# OutputConnectors.net
KiCad netlist of a schematic drawn in Altium Designer
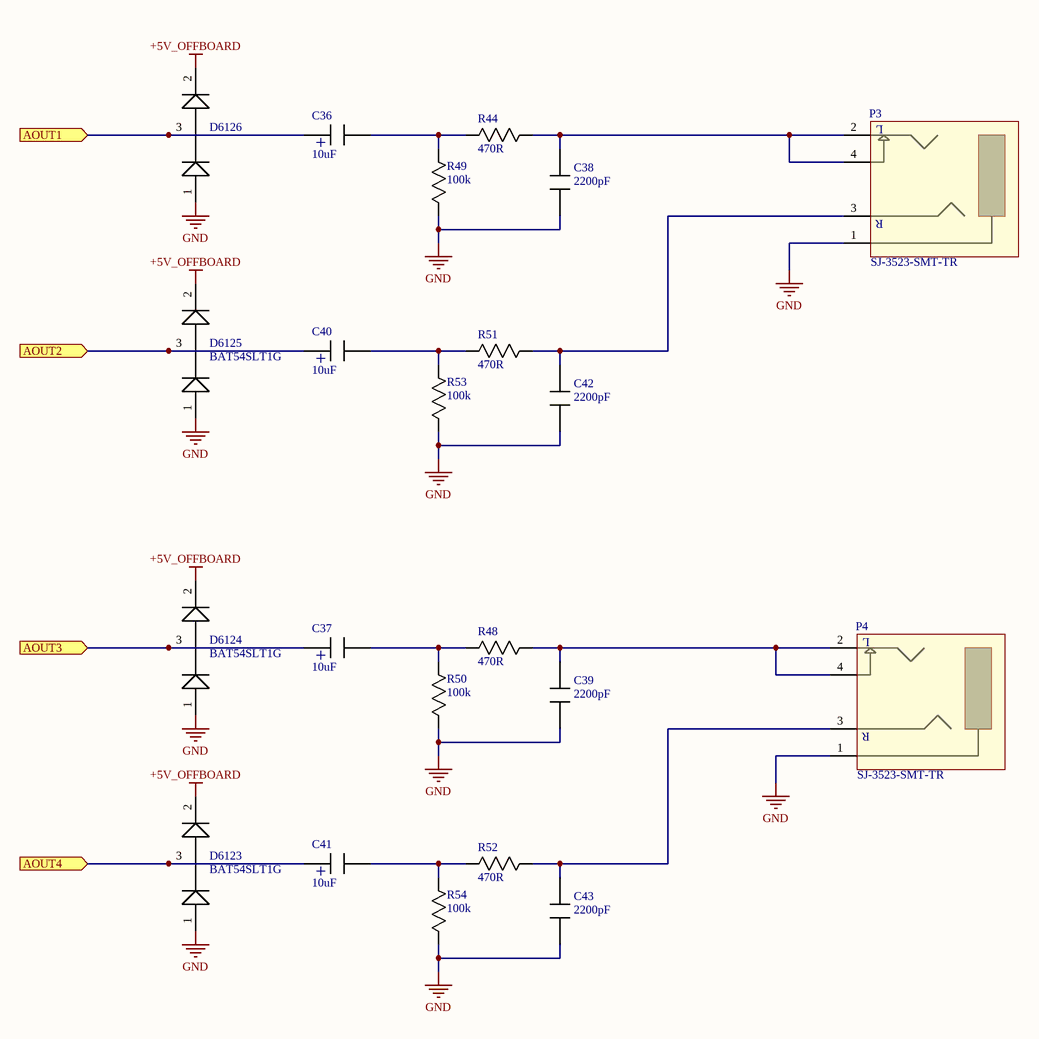
[diagram p0: OutputConnectors.SchDoc]

(export (version "E")
  (design (tool "Eeschema 10.0.6"))
  (components
    (comp (ref "C36")
      (value "10uF")
      (footprint "CAP_RAD_SMD_DIA157")
      (description "Capacitor")
      (fields (field (name "Comment") "Capacitor_Polarized"))
      (libsource (lib "INTER_2014") (part "Capacitor_Polarized"))
    )
    (comp (ref "C37")
      (value "10uF")
      (footprint "CAP_RAD_SMD_DIA157")
      (description "Capacitor")
      (fields (field (name "Comment") "Capacitor_Polarized"))
      (libsource (lib "INTER_2014") (part "Capacitor_Polarized"))
    )
    (comp (ref "C38")
      (value "2200pF")
      (footprint "0603")
      (description "Capacitor")
      (libsource (lib "INTER_2014") (part "Capacitor"))
    )
    (comp (ref "C39")
      (value "2200pF")
      (footprint "0603")
      (description "Capacitor")
      (libsource (lib "INTER_2014") (part "Capacitor"))
    )
    (comp (ref "C40")
      (value "10uF")
      (footprint "CAP_RAD_SMD_DIA157")
      (description "Capacitor")
      (fields (field (name "Comment") "Capacitor_Polarized"))
      (libsource (lib "INTER_2014") (part "Capacitor_Polarized"))
    )
    (comp (ref "C41")
      (value "10uF")
      (footprint "CAP_RAD_SMD_DIA157")
      (description "Capacitor")
      (fields (field (name "Comment") "Capacitor_Polarized"))
      (libsource (lib "INTER_2014") (part "Capacitor_Polarized"))
    )
    (comp (ref "C42")
      (value "2200pF")
      (footprint "0603")
      (description "Capacitor")
      (libsource (lib "INTER_2014") (part "Capacitor"))
    )
    (comp (ref "C43")
      (value "2200pF")
      (footprint "0603")
      (description "Capacitor")
      (libsource (lib "INTER_2014") (part "Capacitor"))
    )
    (comp (ref "D6123")
      (value "Diode_dual")
      (footprint "SOT23_132")
      (description "Diode")
      (fields (field (name "MFG") "Onsemi") (field (name "MFG_PN") "BAT54SLT1G"))
      (libsource (lib "INTER_2014") (part "Diode_dual"))
    )
    (comp (ref "D6124")
      (value "Diode_dual")
      (footprint "SOT23_132")
      (description "Diode")
      (fields (field (name "MFG") "Onsemi") (field (name "MFG_PN") "BAT54SLT1G"))
      (libsource (lib "INTER_2014") (part "Diode_dual"))
    )
    (comp (ref "D6125")
      (value "Diode_dual")
      (footprint "SOT23_132")
      (description "Diode")
      (fields (field (name "MFG") "Onsemi") (field (name "MFG_PN") "BAT54SLT1G"))
      (libsource (lib "INTER_2014") (part "Diode_dual"))
    )
    (comp (ref "D6126")
      (value "Diode_dual")
      (footprint "SOT23_132")
      (description "Diode")
      (fields (field (name "MFG") "Onsemi"))
      (libsource (lib "INTER_2014") (part "Diode_dual"))
    )
    (comp (ref "P3")
      (value "CON_AUDIO_3.5mm_TRS_ALT1")
      (footprint "CONN_3.5mm_CUI 3523-SMT")
      (description "Audio 3.5mm CUI SJ-3523-SMT-TR")
      (fields (field (name "MFG") "CUI") (field (name "MFG_PN") "SJ-3523-SMT-TR"))
      (libsource (lib "INTER_2014") (part "CON_AUDIO_3.5mm_TRS_ALT1"))
    )
    (comp (ref "P4")
      (value "CON_AUDIO_3.5mm_TRS_ALT1")
      (footprint "CONN_3.5mm_CUI 3523-SMT")
      (description "Audio 3.5mm CUI SJ-3523-SMT-TR")
      (fields (field (name "MFG") "CUI") (field (name "MFG_PN") "SJ-3523-SMT-TR"))
      (libsource (lib "INTER_2014") (part "CON_AUDIO_3.5mm_TRS_ALT1"))
    )
    (comp (ref "R44")
      (value "470R")
      (footprint "0603")
      (description "Resistor")
      (libsource (lib "INTER_2014") (part "Resistor"))
    )
    (comp (ref "R48")
      (value "470R")
      (footprint "0603")
      (description "Resistor")
      (libsource (lib "INTER_2014") (part "Resistor"))
    )
    (comp (ref "R49")
      (value "100k")
      (footprint "0603")
      (description "Resistor")
      (libsource (lib "INTER_2014") (part "Resistor"))
    )
    (comp (ref "R50")
      (value "100k")
      (footprint "0603")
      (description "Resistor")
      (libsource (lib "INTER_2014") (part "Resistor"))
    )
    (comp (ref "R51")
      (value "470R")
      (footprint "0603")
      (description "Resistor")
      (libsource (lib "INTER_2014") (part "Resistor"))
    )
    (comp (ref "R52")
      (value "470R")
      (footprint "0603")
      (description "Resistor")
      (libsource (lib "INTER_2014") (part "Resistor"))
    )
    (comp (ref "R53")
      (value "100k")
      (footprint "0603")
      (description "Resistor")
      (libsource (lib "INTER_2014") (part "Resistor"))
    )
    (comp (ref "R54")
      (value "100k")
      (footprint "0603")
      (description "Resistor")
      (libsource (lib "INTER_2014") (part "Resistor"))
    )
  )
  (nets
    (net (code "1") (name "+5V_OFFBOARD") (class "Default")
      (node (ref "D6123") (pin "2") (pinfunction "K_2") (pintype "passive"))
      (node (ref "D6124") (pin "2") (pinfunction "K_2") (pintype "passive"))
      (node (ref "D6125") (pin "2") (pinfunction "K_2") (pintype "passive"))
      (node (ref "D6126") (pin "2") (pinfunction "K_2") (pintype "passive"))
    )
    (net (code "2") (name "/AOUT1") (class "Default")
      (node (ref "C36") (pin "+") (pintype "passive"))
      (node (ref "D6126") (pin "3") (pinfunction "AK_3") (pintype "passive"))
    )
    (net (code "3") (name "/AOUT2") (class "Default")
      (node (ref "C40") (pin "+") (pintype "passive"))
      (node (ref "D6125") (pin "3") (pinfunction "AK_3") (pintype "passive"))
    )
    (net (code "4") (name "/AOUT3") (class "Default")
      (node (ref "C37") (pin "+") (pintype "passive"))
      (node (ref "D6124") (pin "3") (pinfunction "AK_3") (pintype "passive"))
    )
    (net (code "5") (name "/AOUT4") (class "Default")
      (node (ref "C41") (pin "+") (pintype "passive"))
      (node (ref "D6123") (pin "3") (pinfunction "AK_3") (pintype "passive"))
    )
    (net (code "6") (name "GND") (class "Default")
      (node (ref "C38") (pin "2") (pintype "passive"))
      (node (ref "C39") (pin "2") (pintype "passive"))
      (node (ref "C42") (pin "2") (pintype "passive"))
      (node (ref "C43") (pin "2") (pintype "passive"))
      (node (ref "D6123") (pin "1") (pinfunction "K_1") (pintype "passive"))
      (node (ref "D6124") (pin "1") (pinfunction "K_1") (pintype "passive"))
      (node (ref "D6125") (pin "1") (pinfunction "K_1") (pintype "passive"))
      (node (ref "D6126") (pin "1") (pinfunction "K_1") (pintype "passive"))
      (node (ref "P3") (pin "1") (pintype "passive"))
      (node (ref "P4") (pin "1") (pintype "passive"))
      (node (ref "R49") (pin "1") (pintype "passive"))
      (node (ref "R50") (pin "1") (pintype "passive"))
      (node (ref "R53") (pin "1") (pintype "passive"))
      (node (ref "R54") (pin "1") (pintype "passive"))
    )
    (net (code "7") (name "Net-(C36-Pad-)") (class "Default")
      (node (ref "C36") (pin "-") (pintype "passive"))
      (node (ref "R44") (pin "1") (pintype "passive"))
      (node (ref "R49") (pin "2") (pintype "passive"))
    )
    (net (code "8") (name "Net-(C37-Pad-)") (class "Default")
      (node (ref "C37") (pin "-") (pintype "passive"))
      (node (ref "R48") (pin "1") (pintype "passive"))
      (node (ref "R50") (pin "2") (pintype "passive"))
    )
    (net (code "9") (name "Net-(C40-Pad-)") (class "Default")
      (node (ref "C40") (pin "-") (pintype "passive"))
      (node (ref "R51") (pin "1") (pintype "passive"))
      (node (ref "R53") (pin "2") (pintype "passive"))
    )
    (net (code "10") (name "Net-(C41-Pad-)") (class "Default")
      (node (ref "C41") (pin "-") (pintype "passive"))
      (node (ref "R52") (pin "1") (pintype "passive"))
      (node (ref "R54") (pin "2") (pintype "passive"))
    )
    (net (code "11") (name "Net-(P3-L)") (class "Default")
      (node (ref "C38") (pin "1") (pintype "passive"))
      (node (ref "P3") (pin "2") (pinfunction "L_2") (pintype "passive"))
      (node (ref "P3") (pin "4") (pinfunction "NC_L_4") (pintype "passive"))
      (node (ref "R44") (pin "2") (pintype "passive"))
    )
    (net (code "12") (name "Net-(P3-R)") (class "Default")
      (node (ref "C42") (pin "1") (pintype "passive"))
      (node (ref "P3") (pin "3") (pinfunction "R_3") (pintype "passive"))
      (node (ref "R51") (pin "2") (pintype "passive"))
    )
    (net (code "13") (name "Net-(P4-L)") (class "Default")
      (node (ref "C39") (pin "1") (pintype "passive"))
      (node (ref "P4") (pin "2") (pinfunction "L_2") (pintype "passive"))
      (node (ref "P4") (pin "4") (pinfunction "NC_L_4") (pintype "passive"))
      (node (ref "R48") (pin "2") (pintype "passive"))
    )
    (net (code "14") (name "Net-(P4-R)") (class "Default")
      (node (ref "C43") (pin "1") (pintype "passive"))
      (node (ref "P4") (pin "3") (pinfunction "R_3") (pintype "passive"))
      (node (ref "R52") (pin "2") (pintype "passive"))
    )
  )
)
